# espwithULN2003A.net
KiCad netlist of a schematic drawn in EasyEDA
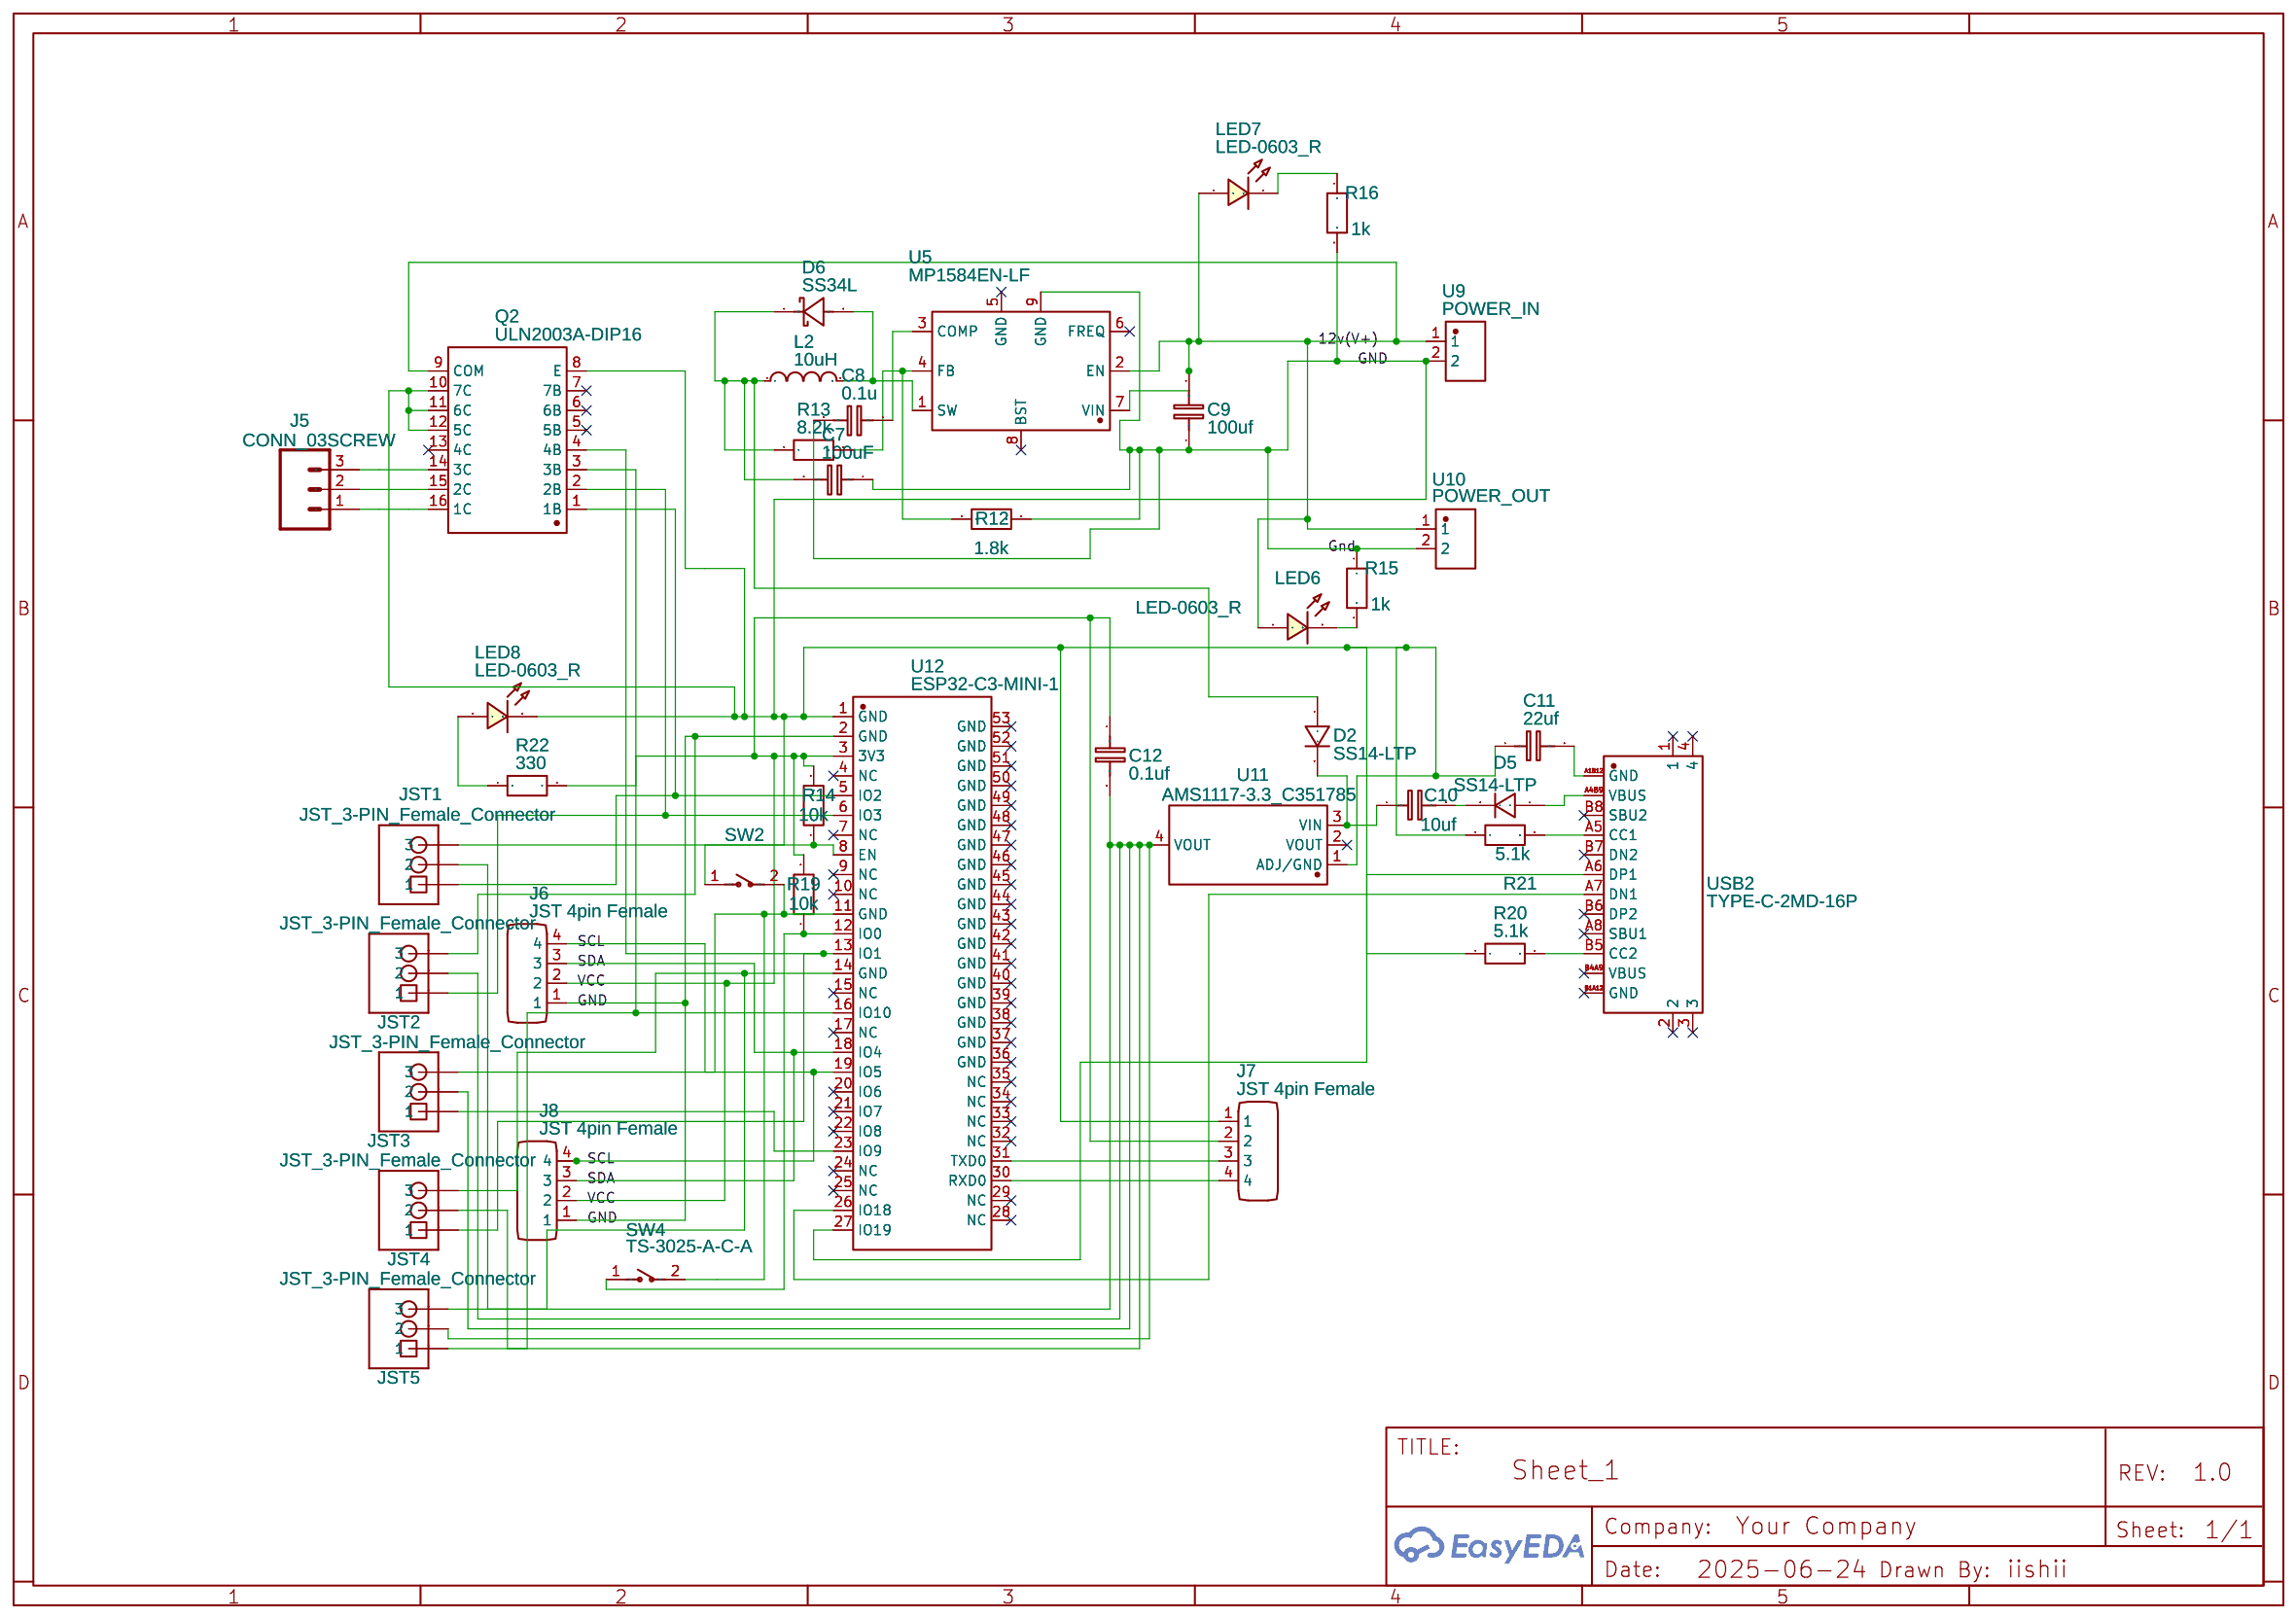
[diagram p0: schematic sheet]

(export (version "E")
  (design (tool "Eeschema 10.0.6"))
  (components
    (comp (ref "C7") (value "100uF") (libsource (lib "") (part "C_0603_EU")))
    (comp (ref "C8") (value "0.1u") (libsource (lib "") (part "C_0603_EU")))
    (comp (ref "C9") (value "100uf") (libsource (lib "") (part "C_0603_EU_2")))
    (comp (ref "C10") (value "10uf") (libsource (lib "") (part "C_0603_EU_1")))
    (comp (ref "C11") (value "22uf") (libsource (lib "") (part "C_0603_EU_1")))
    (comp (ref "C12") (value "0.1uf") (libsource (lib "") (part "C_0603_EU_3")))
    (comp (ref "D2")
      (value "SS14-LTP")
      (fields (field (name "Manufacturer") "MCC(美微科)"))
      (libsource (lib "") (part "SS14-LTP_1"))
    )
    (comp (ref "D5")
      (value "SS14-LTP")
      (fields (field (name "Manufacturer") "MCC(美微科)"))
      (libsource (lib "") (part "SS14-LTP"))
    )
    (comp (ref "D6")
      (value "SS34L")
      (fields (field (name "Manufacturer") "Hottech(合科泰)"))
      (libsource (lib "") (part "SS34L"))
    )
    (comp (ref "J5") (value "CONN_03SCREW") (libsource (lib "") (part "CONN_03SCREW")))
    (comp (ref "J6") (value "JST 4pin Female") (libsource (lib "") (part "JST 4pin Female")))
    (comp (ref "J7") (value "JST 4pin Female") (libsource (lib "") (part "JST 4pin Female_1")))
    (comp (ref "J8") (value "JST 4pin Female") (libsource (lib "") (part "JST 4pin Female")))
    (comp (ref "JST1")
      (value "JST_3-PIN_Female_Connector")
      (libsource (lib "") (part "JST_3-PIN_Female_Connector"))
    )
    (comp (ref "JST2")
      (value "JST_3-PIN_Female_Connector")
      (libsource (lib "") (part "JST_3-PIN_Female_Connector"))
    )
    (comp (ref "JST3")
      (value "JST_3-PIN_Female_Connector")
      (libsource (lib "") (part "JST_3-PIN_Female_Connector"))
    )
    (comp (ref "JST4")
      (value "JST_3-PIN_Female_Connector")
      (libsource (lib "") (part "JST_3-PIN_Female_Connector"))
    )
    (comp (ref "JST5")
      (value "JST_3-PIN_Female_Connector")
      (libsource (lib "") (part "JST_3-PIN_Female_Connector"))
    )
    (comp (ref "L2") (value "10uH") (libsource (lib "") (part "L0603_US")))
    (comp (ref "LED6")
      (value "LED-0603_R")
      (fields
        (field (name "Manufacturer Part") "19-217/R6C-AL1M2VY/3T")
        (field (name "Manufacturer") "EVERLIGHT(台湾亿光)")
      )
      (libsource (lib "") (part "LED-0603_R"))
    )
    (comp (ref "LED7")
      (value "LED-0603_R")
      (fields
        (field (name "Manufacturer Part") "19-217/R6C-AL1M2VY/3T")
        (field (name "Manufacturer") "EVERLIGHT(台湾亿光)")
      )
      (libsource (lib "") (part "LED-0603_R"))
    )
    (comp (ref "LED8")
      (value "LED-0603_R")
      (fields
        (field (name "Manufacturer Part") "19-217/R6C-AL1M2VY/3T")
        (field (name "Manufacturer") "EVERLIGHT(台湾亿光)")
      )
      (libsource (lib "") (part "LED-0603_R"))
    )
    (comp (ref "Q2")
      (value "ULN2003A-DIP16")
      (fields (field (name "Manufacturer") "Mixic(中科芯亿达)"))
      (libsource (lib "") (part "ULN2003A-DIP16"))
    )
    (comp (ref "R12") (value "1.8k") (libsource (lib "") (part "R_0603_EU")))
    (comp (ref "R13") (value "8.2k") (libsource (lib "") (part "R_0603_EU")))
    (comp (ref "R14") (value "10k") (libsource (lib "") (part "R_0603_EU_1")))
    (comp (ref "R15") (value "1k") (libsource (lib "") (part "R_0603_EU_2")))
    (comp (ref "R16") (value "1k") (libsource (lib "") (part "R_0603_EU_2")))
    (comp (ref "R19") (value "10k") (libsource (lib "") (part "R_0603_EU_1")))
    (comp (ref "R20") (value "5.1k") (libsource (lib "") (part "R_0603_EU")))
    (comp (ref "R21") (value "5.1k") (libsource (lib "") (part "R_0603_EU")))
    (comp (ref "R22") (value "330") (libsource (lib "") (part "R_0603_EU")))
    (comp (ref "SW2")
      (value "TS-3025-A-C-A")
      (fields (field (name "Manufacturer") "XKB Connection(中国星坤)"))
      (libsource (lib "") (part "TS-3025-A-C-A"))
    )
    (comp (ref "SW4")
      (value "TS-3025-A-C-A")
      (fields (field (name "Manufacturer") "XKB Connection(中国星坤)"))
      (libsource (lib "") (part "TS-3025-A-C-A"))
    )
    (comp (ref "U5")
      (value "MP1584EN-LF")
      (fields (field (name "Manufacturer") "MPS(芯源)"))
      (libsource (lib "") (part "MP1584EN-LF"))
    )
    (comp (ref "U9")
      (value "POWER_IN")
      (fields (field (name "Manufacturer Part") "JST-B2PS-VH(LF)(SN)黑色"))
      (libsource (lib "") (part "JST-B2PS-VH(LF)(SN)黑色"))
    )
    (comp (ref "U10")
      (value "POWER_OUT")
      (fields (field (name "Manufacturer Part") "JST-B2PS-VH(LF)(SN)黑色"))
      (libsource (lib "") (part "JST-B2PS-VH(LF)(SN)黑色"))
    )
    (comp (ref "U11")
      (value "AMS1117-3.3_C351785")
      (fields (field (name "Manufacturer Part") "AMS1117-3.3") (field (name "Manufacturer") "PUOLOP(迪浦)"))
      (libsource (lib "") (part "AMS1117-3.3_C351785"))
    )
    (comp (ref "U12")
      (value "ESP32-C3-MINI-1")
      (fields (field (name "Manufacturer") "RF Crazy(智汉)"))
      (libsource (lib "") (part "ESP32-C3-MINI-1"))
    )
    (comp (ref "USB2")
      (value "TYPE-C-2MD-16P")
      (fields (field (name "Manufacturer") "JXTCONN(聚兴泰)"))
      (libsource (lib "") (part "TYPE-C-2MD-16P"))
    )
  )
  (nets
    (net (code "1") (name "/12v(V+)") (class "Default")
      (node (ref "C9") (pin "2") (pinfunction "2_2") (pintype "unspecified"))
      (node (ref "LED6") (pin "1") (pinfunction "1_1") (pintype "unspecified"))
      (node (ref "LED7") (pin "1") (pinfunction "1_1") (pintype "unspecified"))
      (node (ref "Q2") (pin "9") (pinfunction "COM_9") (pintype "unspecified"))
      (node (ref "U10") (pin "1") (pinfunction "1_1") (pintype "unspecified"))
      (node (ref "U5") (pin "2") (pinfunction "EN_2") (pintype "unspecified"))
      (node (ref "U5") (pin "7") (pinfunction "VIN_7") (pintype "unspecified"))
      (node (ref "U9") (pin "1") (pinfunction "1_1") (pintype "unspecified"))
    )
    (net (code "2") (name "/GND") (class "Default")
      (node (ref "C11") (pin "1") (pinfunction "1_1") (pintype "unspecified"))
      (node (ref "C7") (pin "1") (pinfunction "1_1") (pintype "unspecified"))
      (node (ref "C8") (pin "2") (pinfunction "2_2") (pintype "unspecified"))
      (node (ref "C9") (pin "1") (pinfunction "1_1") (pintype "unspecified"))
      (node (ref "J6") (pin "1") (pinfunction "1_1") (pintype "unspecified"))
      (node (ref "J7") (pin "1") (pinfunction "1_1") (pintype "unspecified"))
      (node (ref "J8") (pin "1") (pinfunction "1_1") (pintype "unspecified"))
      (node (ref "JST1") (pin "3") (pinfunction "3_3") (pintype "unspecified"))
      (node (ref "JST2") (pin "3") (pinfunction "3_3") (pintype "unspecified"))
      (node (ref "LED8") (pin "2") (pinfunction "2_2") (pintype "unspecified"))
      (node (ref "Q2") (pin "10") (pinfunction "7C_10") (pintype "unspecified"))
      (node (ref "Q2") (pin "11") (pinfunction "6C_11") (pintype "unspecified"))
      (node (ref "Q2") (pin "12") (pinfunction "5C_12") (pintype "unspecified"))
      (node (ref "Q2") (pin "8") (pinfunction "E_8") (pintype "unspecified"))
      (node (ref "R12") (pin "2") (pinfunction "2_2") (pintype "unspecified"))
      (node (ref "R15") (pin "1") (pinfunction "1_1") (pintype "unspecified"))
      (node (ref "R16") (pin "2") (pinfunction "2_2") (pintype "unspecified"))
      (node (ref "R20") (pin "1") (pinfunction "1_1") (pintype "unspecified"))
      (node (ref "R21") (pin "1") (pinfunction "1_1") (pintype "unspecified"))
      (node (ref "U10") (pin "2") (pinfunction "2_2") (pintype "unspecified"))
      (node (ref "U11") (pin "1") (pinfunction "ADJ/GND_1") (pintype "unspecified"))
      (node (ref "U12") (pin "1") (pinfunction "GND_1") (pintype "unspecified"))
      (node (ref "U12") (pin "2") (pinfunction "GND_2") (pintype "unspecified"))
      (node (ref "U5") (pin "9") (pinfunction "GND_9") (pintype "unspecified"))
      (node (ref "U9") (pin "2") (pinfunction "2_2") (pintype "unspecified"))
    )
    (net (code "3") (name "/SCL") (class "Default")
      (node (ref "J6") (pin "4") (pinfunction "4_4") (pintype "unspecified"))
      (node (ref "J8") (pin "4") (pinfunction "4_4") (pintype "unspecified"))
      (node (ref "U12") (pin "19") (pinfunction "IO5_19") (pintype "unspecified"))
    )
    (net (code "4") (name "/SDA") (class "Default")
      (node (ref "J6") (pin "3") (pinfunction "3_3") (pintype "unspecified"))
      (node (ref "J8") (pin "3") (pinfunction "3_3") (pintype "unspecified"))
      (node (ref "U12") (pin "18") (pinfunction "IO4_18") (pintype "unspecified"))
    )
    (net (code "5") (name "/VCC") (class "Default")
      (node (ref "C12") (pin "1") (pinfunction "1_1") (pintype "unspecified"))
      (node (ref "J6") (pin "2") (pinfunction "2_2") (pintype "unspecified"))
      (node (ref "J7") (pin "2") (pinfunction "2_2") (pintype "unspecified"))
      (node (ref "J8") (pin "2") (pinfunction "2_2") (pintype "unspecified"))
      (node (ref "R14") (pin "2") (pinfunction "2_2") (pintype "unspecified"))
      (node (ref "R19") (pin "2") (pinfunction "2_2") (pintype "unspecified"))
      (node (ref "R22") (pin "2") (pinfunction "2_2") (pintype "unspecified"))
      (node (ref "U12") (pin "3") (pinfunction "3V3_3") (pintype "unspecified"))
    )
    (net (code "6") (name "Net-(C11-Pad2)") (class "Default")
      (node (ref "C11") (pin "2") (pinfunction "2_2") (pintype "unspecified"))
      (node (ref "USB2") (pin "A1B12") (pinfunction "GND_A1B12") (pintype "unspecified"))
    )
    (net (code "7") (name "Net-(C12-Pad2)") (class "Default")
      (node (ref "C12") (pin "2") (pinfunction "2_2") (pintype "unspecified"))
      (node (ref "JST1") (pin "2") (pinfunction "2_2") (pintype "unspecified"))
      (node (ref "JST2") (pin "2") (pinfunction "2_2") (pintype "unspecified"))
      (node (ref "JST3") (pin "2") (pinfunction "2_2") (pintype "unspecified"))
      (node (ref "JST4") (pin "2") (pinfunction "2_2") (pintype "unspecified"))
      (node (ref "JST5") (pin "2") (pinfunction "2_2") (pintype "unspecified"))
      (node (ref "U11") (pin "4") (pinfunction "VOUT_4") (pintype "unspecified"))
    )
    (net (code "8") (name "Net-(D2-A)") (class "Default")
      (node (ref "C7") (pin "2") (pinfunction "2_2") (pintype "unspecified"))
      (node (ref "D2") (pin "1") (pinfunction "A_1") (pintype "unspecified"))
      (node (ref "D6") (pin "1") (pinfunction "C_1") (pintype "unspecified"))
      (node (ref "L2") (pin "1") (pinfunction "1_1") (pintype "unspecified"))
      (node (ref "R13") (pin "1") (pinfunction "1_1") (pintype "unspecified"))
    )
    (net (code "9") (name "Net-(D2-K)") (class "Default")
      (node (ref "C10") (pin "1") (pinfunction "1_1") (pintype "unspecified"))
      (node (ref "D2") (pin "2") (pinfunction "K_2") (pintype "unspecified"))
      (node (ref "U11") (pin "3") (pinfunction "VIN_3") (pintype "unspecified"))
    )
    (net (code "10") (name "Net-(D5-A)") (class "Default")
      (node (ref "D5") (pin "1") (pinfunction "A_1") (pintype "unspecified"))
      (node (ref "USB2") (pin "A4B9") (pinfunction "VBUS_A4B9") (pintype "unspecified"))
    )
    (net (code "11") (name "Net-(D5-K)") (class "Default")
      (node (ref "C10") (pin "2") (pinfunction "2_2") (pintype "unspecified"))
      (node (ref "D5") (pin "2") (pinfunction "K_2") (pintype "unspecified"))
    )
    (net (code "12") (name "Net-(D6-A)") (class "Default")
      (node (ref "D6") (pin "2") (pinfunction "A_2") (pintype "unspecified"))
      (node (ref "L2") (pin "2") (pinfunction "2_2") (pintype "unspecified"))
      (node (ref "U5") (pin "1") (pinfunction "SW_1") (pintype "unspecified"))
    )
    (net (code "13") (name "Net-(JST3-Pad3)") (class "Default")
      (node (ref "JST3") (pin "3") (pinfunction "3_3") (pintype "unspecified"))
      (node (ref "SW2") (pin "2") (pinfunction "2_2") (pintype "unspecified"))
      (node (ref "SW4") (pin "2") (pinfunction "2_2") (pintype "unspecified"))
      (node (ref "U12") (pin "11") (pinfunction "GND_11") (pintype "unspecified"))
    )
    (net (code "14") (name "Net-(JST4-Pad3)") (class "Default")
      (node (ref "JST4") (pin "3") (pinfunction "3_3") (pintype "unspecified"))
      (node (ref "JST5") (pin "3") (pinfunction "3_3") (pintype "unspecified"))
      (node (ref "U12") (pin "14") (pinfunction "GND_14") (pintype "unspecified"))
    )
    (net (code "15") (name "Net-(LED6-Pad2)") (class "Default")
      (node (ref "LED6") (pin "2") (pinfunction "2_2") (pintype "unspecified"))
      (node (ref "R15") (pin "2") (pinfunction "2_2") (pintype "unspecified"))
    )
    (net (code "16") (name "Net-(LED7-Pad2)") (class "Default")
      (node (ref "LED7") (pin "2") (pinfunction "2_2") (pintype "unspecified"))
      (node (ref "R16") (pin "1") (pinfunction "1_1") (pintype "unspecified"))
    )
    (net (code "17") (name "Net-(LED8-Pad1)") (class "Default")
      (node (ref "LED8") (pin "1") (pinfunction "1_1") (pintype "unspecified"))
      (node (ref "R22") (pin "1") (pinfunction "1_1") (pintype "unspecified"))
    )
    (net (code "18") (name "Net-(Q2-1B)") (class "Default")
      (node (ref "JST1") (pin "1") (pinfunction "1_1") (pintype "unspecified"))
      (node (ref "Q2") (pin "1") (pinfunction "1B_1") (pintype "unspecified"))
      (node (ref "U12") (pin "5") (pinfunction "IO2_5") (pintype "unspecified"))
    )
    (net (code "19") (name "Net-(Q2-1C)") (class "Default")
      (node (ref "J5") (pin "1") (pinfunction "1_1") (pintype "bidirectional"))
      (node (ref "Q2") (pin "16") (pinfunction "1C_16") (pintype "unspecified"))
    )
    (net (code "20") (name "Net-(Q2-2B)") (class "Default")
      (node (ref "JST2") (pin "1") (pinfunction "1_1") (pintype "unspecified"))
      (node (ref "Q2") (pin "2") (pinfunction "2B_2") (pintype "unspecified"))
      (node (ref "U12") (pin "6") (pinfunction "IO3_6") (pintype "unspecified"))
    )
    (net (code "21") (name "Net-(Q2-2C)") (class "Default")
      (node (ref "J5") (pin "2") (pinfunction "2_2") (pintype "bidirectional"))
      (node (ref "Q2") (pin "15") (pinfunction "2C_15") (pintype "unspecified"))
    )
    (net (code "22") (name "Net-(Q2-3B)") (class "Default")
      (node (ref "JST5") (pin "1") (pinfunction "1_1") (pintype "unspecified"))
      (node (ref "Q2") (pin "3") (pinfunction "3B_3") (pintype "unspecified"))
      (node (ref "U12") (pin "16") (pinfunction "IO10_16") (pintype "unspecified"))
    )
    (net (code "23") (name "Net-(Q2-3C)") (class "Default")
      (node (ref "J5") (pin "3") (pinfunction "3_3") (pintype "bidirectional"))
      (node (ref "Q2") (pin "14") (pinfunction "3C_14") (pintype "unspecified"))
    )
    (net (code "24") (name "Net-(Q2-4B)") (class "Default")
      (node (ref "JST4") (pin "1") (pinfunction "1_1") (pintype "unspecified"))
      (node (ref "Q2") (pin "4") (pinfunction "4B_4") (pintype "unspecified"))
      (node (ref "U12") (pin "13") (pinfunction "IO1_13") (pintype "unspecified"))
    )
    (net (code "25") (name "Net-(U5-COMP)") (class "Default")
      (node (ref "C8") (pin "1") (pinfunction "1_1") (pintype "unspecified"))
      (node (ref "U5") (pin "3") (pinfunction "COMP_3") (pintype "unspecified"))
    )
    (net (code "26") (name "Net-(U5-FB)") (class "Default")
      (node (ref "R12") (pin "1") (pinfunction "1_1") (pintype "unspecified"))
      (node (ref "R13") (pin "2") (pinfunction "2_2") (pintype "unspecified"))
      (node (ref "U5") (pin "4") (pinfunction "FB_4") (pintype "unspecified"))
    )
    (net (code "27") (name "Net-(U12-EN)") (class "Default")
      (node (ref "R14") (pin "1") (pinfunction "1_1") (pintype "unspecified"))
      (node (ref "SW2") (pin "1") (pinfunction "1_1") (pintype "unspecified"))
      (node (ref "U12") (pin "8") (pinfunction "EN_8") (pintype "unspecified"))
    )
    (net (code "28") (name "Net-(U12-IO0)") (class "Default")
      (node (ref "R19") (pin "1") (pinfunction "1_1") (pintype "unspecified"))
      (node (ref "SW4") (pin "1") (pinfunction "1_1") (pintype "unspecified"))
      (node (ref "U12") (pin "12") (pinfunction "IO0_12") (pintype "unspecified"))
    )
    (net (code "29") (name "Net-(U12-IO9)") (class "Default")
      (node (ref "JST3") (pin "1") (pinfunction "1_1") (pintype "unspecified"))
      (node (ref "U12") (pin "23") (pinfunction "IO9_23") (pintype "unspecified"))
    )
    (net (code "30") (name "Net-(U12-IO18)") (class "Default")
      (node (ref "U12") (pin "26") (pinfunction "IO18_26") (pintype "unspecified"))
      (node (ref "USB2") (pin "A7") (pinfunction "DN1_A7") (pintype "unspecified"))
    )
    (net (code "31") (name "Net-(U12-IO19)") (class "Default")
      (node (ref "U12") (pin "27") (pinfunction "IO19_27") (pintype "unspecified"))
      (node (ref "USB2") (pin "A6") (pinfunction "DP1_A6") (pintype "unspecified"))
    )
    (net (code "32") (name "Net-(U12-RXD0)") (class "Default")
      (node (ref "J7") (pin "4") (pinfunction "4_4") (pintype "unspecified"))
      (node (ref "U12") (pin "30") (pinfunction "RXD0_30") (pintype "unspecified"))
    )
    (net (code "33") (name "Net-(U12-TXD0)") (class "Default")
      (node (ref "J7") (pin "3") (pinfunction "3_3") (pintype "unspecified"))
      (node (ref "U12") (pin "31") (pinfunction "TXD0_31") (pintype "unspecified"))
    )
    (net (code "34") (name "Net-(USB2-CC1)") (class "Default")
      (node (ref "R21") (pin "2") (pinfunction "2_2") (pintype "unspecified"))
      (node (ref "USB2") (pin "A5") (pinfunction "CC1_A5") (pintype "unspecified"))
    )
    (net (code "35") (name "Net-(USB2-CC2)") (class "Default")
      (node (ref "R20") (pin "2") (pinfunction "2_2") (pintype "unspecified"))
      (node (ref "USB2") (pin "B5") (pinfunction "CC2_B5") (pintype "unspecified"))
    )
    (net (code "36") (name "unconnected-(Q2-4C-Pad13)") (class "Default")
      (node (ref "Q2") (pin "13") (pinfunction "4C_13") (pintype "unspecified+no_connect"))
    )
    (net (code "37") (name "unconnected-(Q2-5B-Pad5)") (class "Default")
      (node (ref "Q2") (pin "5") (pinfunction "5B_5") (pintype "unspecified+no_connect"))
    )
    (net (code "38") (name "unconnected-(Q2-6B-Pad6)") (class "Default")
      (node (ref "Q2") (pin "6") (pinfunction "6B_6") (pintype "unspecified+no_connect"))
    )
    (net (code "39") (name "unconnected-(Q2-7B-Pad7)") (class "Default")
      (node (ref "Q2") (pin "7") (pinfunction "7B_7") (pintype "unspecified+no_connect"))
    )
    (net (code "40") (name "unconnected-(U5-BST-Pad8)") (class "Default")
      (node (ref "U5") (pin "8") (pinfunction "BST_8") (pintype "unspecified+no_connect"))
    )
    (net (code "41") (name "unconnected-(U5-FREQ-Pad6)") (class "Default")
      (node (ref "U5") (pin "6") (pinfunction "FREQ_6") (pintype "unspecified+no_connect"))
    )
    (net (code "42") (name "unconnected-(U5-GND-Pad5)") (class "Default")
      (node (ref "U5") (pin "5") (pinfunction "GND_5") (pintype "unspecified+no_connect"))
    )
    (net (code "43") (name "unconnected-(U11-VOUT-Pad2)") (class "Default")
      (node (ref "U11") (pin "2") (pinfunction "VOUT_2") (pintype "unspecified+no_connect"))
    )
    (net (code "44") (name "unconnected-(U12-GND-Pad36)") (class "Default")
      (node (ref "U12") (pin "36") (pinfunction "GND_36") (pintype "unspecified+no_connect"))
    )
    (net (code "45") (name "unconnected-(U12-GND-Pad37)") (class "Default")
      (node (ref "U12") (pin "37") (pinfunction "GND_37") (pintype "unspecified+no_connect"))
    )
    (net (code "46") (name "unconnected-(U12-GND-Pad38)") (class "Default")
      (node (ref "U12") (pin "38") (pinfunction "GND_38") (pintype "unspecified+no_connect"))
    )
    (net (code "47") (name "unconnected-(U12-GND-Pad39)") (class "Default")
      (node (ref "U12") (pin "39") (pinfunction "GND_39") (pintype "unspecified+no_connect"))
    )
    (net (code "48") (name "unconnected-(U12-GND-Pad40)") (class "Default")
      (node (ref "U12") (pin "40") (pinfunction "GND_40") (pintype "unspecified+no_connect"))
    )
    (net (code "49") (name "unconnected-(U12-GND-Pad41)") (class "Default")
      (node (ref "U12") (pin "41") (pinfunction "GND_41") (pintype "unspecified+no_connect"))
    )
    (net (code "50") (name "unconnected-(U12-GND-Pad42)") (class "Default")
      (node (ref "U12") (pin "42") (pinfunction "GND_42") (pintype "unspecified+no_connect"))
    )
    (net (code "51") (name "unconnected-(U12-GND-Pad43)") (class "Default")
      (node (ref "U12") (pin "43") (pinfunction "GND_43") (pintype "unspecified+no_connect"))
    )
    (net (code "52") (name "unconnected-(U12-GND-Pad44)") (class "Default")
      (node (ref "U12") (pin "44") (pinfunction "GND_44") (pintype "unspecified+no_connect"))
    )
    (net (code "53") (name "unconnected-(U12-GND-Pad45)") (class "Default")
      (node (ref "U12") (pin "45") (pinfunction "GND_45") (pintype "unspecified+no_connect"))
    )
    (net (code "54") (name "unconnected-(U12-GND-Pad46)") (class "Default")
      (node (ref "U12") (pin "46") (pinfunction "GND_46") (pintype "unspecified+no_connect"))
    )
    (net (code "55") (name "unconnected-(U12-GND-Pad47)") (class "Default")
      (node (ref "U12") (pin "47") (pinfunction "GND_47") (pintype "unspecified+no_connect"))
    )
    (net (code "56") (name "unconnected-(U12-GND-Pad48)") (class "Default")
      (node (ref "U12") (pin "48") (pinfunction "GND_48") (pintype "unspecified+no_connect"))
    )
    (net (code "57") (name "unconnected-(U12-GND-Pad49)") (class "Default")
      (node (ref "U12") (pin "49") (pinfunction "GND_49") (pintype "unspecified+no_connect"))
    )
    (net (code "58") (name "unconnected-(U12-GND-Pad50)") (class "Default")
      (node (ref "U12") (pin "50") (pinfunction "GND_50") (pintype "unspecified+no_connect"))
    )
    (net (code "59") (name "unconnected-(U12-GND-Pad51)") (class "Default")
      (node (ref "U12") (pin "51") (pinfunction "GND_51") (pintype "unspecified+no_connect"))
    )
    (net (code "60") (name "unconnected-(U12-GND-Pad52)") (class "Default")
      (node (ref "U12") (pin "52") (pinfunction "GND_52") (pintype "unspecified+no_connect"))
    )
    (net (code "61") (name "unconnected-(U12-GND-Pad53)") (class "Default")
      (node (ref "U12") (pin "53") (pinfunction "GND_53") (pintype "unspecified+no_connect"))
    )
    (net (code "62") (name "unconnected-(U12-IO6-Pad20)") (class "Default")
      (node (ref "U12") (pin "20") (pinfunction "IO6_20") (pintype "unspecified+no_connect"))
    )
    (net (code "63") (name "unconnected-(U12-IO7-Pad21)") (class "Default")
      (node (ref "U12") (pin "21") (pinfunction "IO7_21") (pintype "unspecified+no_connect"))
    )
    (net (code "64") (name "unconnected-(U12-IO8-Pad22)") (class "Default")
      (node (ref "U12") (pin "22") (pinfunction "IO8_22") (pintype "unspecified+no_connect"))
    )
    (net (code "65") (name "unconnected-(U12-NC-Pad4)") (class "Default")
      (node (ref "U12") (pin "4") (pinfunction "NC_4") (pintype "unspecified+no_connect"))
    )
    (net (code "66") (name "unconnected-(U12-NC-Pad7)") (class "Default")
      (node (ref "U12") (pin "7") (pinfunction "NC_7") (pintype "unspecified+no_connect"))
    )
    (net (code "67") (name "unconnected-(U12-NC-Pad9)") (class "Default")
      (node (ref "U12") (pin "9") (pinfunction "NC_9") (pintype "unspecified+no_connect"))
    )
    (net (code "68") (name "unconnected-(U12-NC-Pad10)") (class "Default")
      (node (ref "U12") (pin "10") (pinfunction "NC_10") (pintype "unspecified+no_connect"))
    )
    (net (code "69") (name "unconnected-(U12-NC-Pad15)") (class "Default")
      (node (ref "U12") (pin "15") (pinfunction "NC_15") (pintype "unspecified+no_connect"))
    )
    (net (code "70") (name "unconnected-(U12-NC-Pad17)") (class "Default")
      (node (ref "U12") (pin "17") (pinfunction "NC_17") (pintype "unspecified+no_connect"))
    )
    (net (code "71") (name "unconnected-(U12-NC-Pad24)") (class "Default")
      (node (ref "U12") (pin "24") (pinfunction "NC_24") (pintype "unspecified+no_connect"))
    )
    (net (code "72") (name "unconnected-(U12-NC-Pad25)") (class "Default")
      (node (ref "U12") (pin "25") (pinfunction "NC_25") (pintype "unspecified+no_connect"))
    )
    (net (code "73") (name "unconnected-(U12-NC-Pad28)") (class "Default")
      (node (ref "U12") (pin "28") (pinfunction "NC_28") (pintype "unspecified+no_connect"))
    )
    (net (code "74") (name "unconnected-(U12-NC-Pad29)") (class "Default")
      (node (ref "U12") (pin "29") (pinfunction "NC_29") (pintype "unspecified+no_connect"))
    )
    (net (code "75") (name "unconnected-(U12-NC-Pad32)") (class "Default")
      (node (ref "U12") (pin "32") (pinfunction "NC_32") (pintype "unspecified+no_connect"))
    )
    (net (code "76") (name "unconnected-(U12-NC-Pad33)") (class "Default")
      (node (ref "U12") (pin "33") (pinfunction "NC_33") (pintype "unspecified+no_connect"))
    )
    (net (code "77") (name "unconnected-(U12-NC-Pad34)") (class "Default")
      (node (ref "U12") (pin "34") (pinfunction "NC_34") (pintype "unspecified+no_connect"))
    )
    (net (code "78") (name "unconnected-(U12-NC-Pad35)") (class "Default")
      (node (ref "U12") (pin "35") (pinfunction "NC_35") (pintype "unspecified+no_connect"))
    )
    (net (code "79") (name "unconnected-(USB2-DN2-PadB7)") (class "Default")
      (node (ref "USB2") (pin "B7") (pinfunction "DN2_B7") (pintype "unspecified+no_connect"))
    )
    (net (code "80") (name "unconnected-(USB2-DP2-PadB6)") (class "Default")
      (node (ref "USB2") (pin "B6") (pinfunction "DP2_B6") (pintype "unspecified+no_connect"))
    )
    (net (code "81") (name "unconnected-(USB2-GND-PadB1A12)") (class "Default")
      (node (ref "USB2") (pin "B1A12") (pinfunction "GND_B1A12") (pintype "unspecified+no_connect"))
    )
    (net (code "82") (name "unconnected-(USB2-Pad1)") (class "Default")
      (node (ref "USB2") (pin "1") (pinfunction "1_1") (pintype "unspecified+no_connect"))
    )
    (net (code "83") (name "unconnected-(USB2-Pad2)") (class "Default")
      (node (ref "USB2") (pin "2") (pinfunction "2_2") (pintype "unspecified+no_connect"))
    )
    (net (code "84") (name "unconnected-(USB2-Pad3)") (class "Default")
      (node (ref "USB2") (pin "3") (pinfunction "3_3") (pintype "unspecified+no_connect"))
    )
    (net (code "85") (name "unconnected-(USB2-Pad4)") (class "Default")
      (node (ref "USB2") (pin "4") (pinfunction "4_4") (pintype "unspecified+no_connect"))
    )
    (net (code "86") (name "unconnected-(USB2-SBU1-PadA8)") (class "Default")
      (node (ref "USB2") (pin "A8") (pinfunction "SBU1_A8") (pintype "unspecified+no_connect"))
    )
    (net (code "87") (name "unconnected-(USB2-SBU2-PadB8)") (class "Default")
      (node (ref "USB2") (pin "B8") (pinfunction "SBU2_B8") (pintype "unspecified+no_connect"))
    )
    (net (code "88") (name "unconnected-(USB2-VBUS-PadB4A9)") (class "Default")
      (node (ref "USB2") (pin "B4A9") (pinfunction "VBUS_B4A9") (pintype "unspecified+no_connect"))
    )
  )
)
